# APRS-ESP32_SA8x8_Rev_D.net
KiCad netlist of a schematic drawn in EAGLE
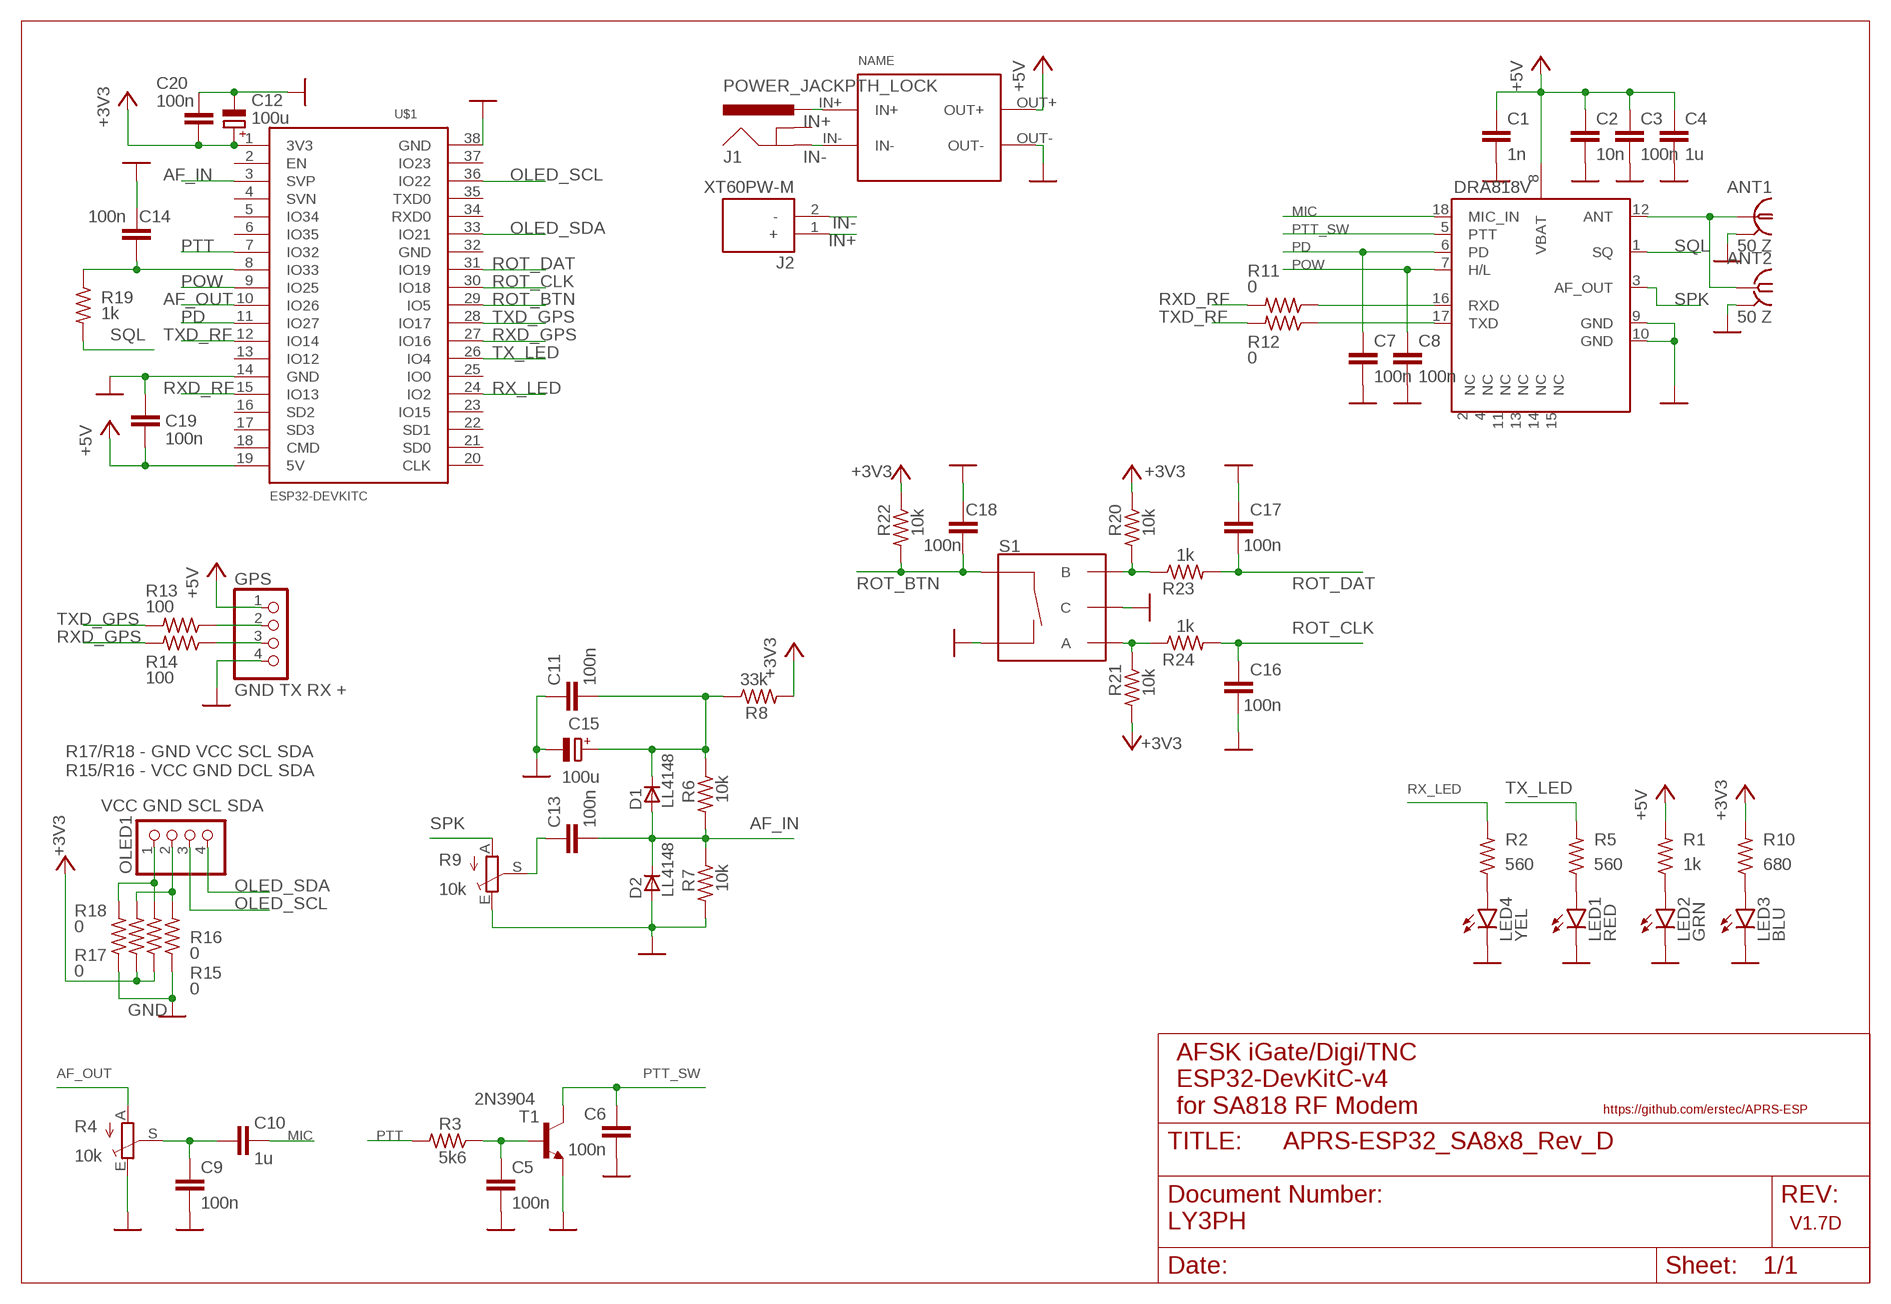
[diagram p0: schematic, sheet 1]

(export (version "E")
  (design (tool "Eeschema 10.0.6"))
  (components
    (comp (ref "ANT1")
      (value "50 Z")
      (footprint "eagle-import:LTI-SASF54GT")
      (libsource (lib "eagle-import") (part "LTI-SASF54GT"))
    )
    (comp (ref "ANT2")
      (value "50 Z")
      (footprint "eagle-import:J502-ND-142-0701-801_806")
      (fields (field (name "MF") "JOHNSON COMPONENTS") (field (name "MPN") "142-0701-801"))
      (libsource (lib "eagle-import") (part "SMA-142-0701-801/806"))
    )
    (comp (ref "C1")
      (value "1n")
      (footprint "eagle-import:C0805")
      (libsource (lib "eagle-import") (part "C-EUC0805"))
    )
    (comp (ref "C2")
      (value "10n")
      (footprint "eagle-import:C0805")
      (libsource (lib "eagle-import") (part "C-EUC0805"))
    )
    (comp (ref "C3")
      (value "100n")
      (footprint "eagle-import:C0805")
      (libsource (lib "eagle-import") (part "C-EUC0805"))
    )
    (comp (ref "C4")
      (value "1u")
      (footprint "eagle-import:C0805")
      (libsource (lib "eagle-import") (part "C-EUC0805"))
    )
    (comp (ref "C5")
      (value "100n")
      (footprint "eagle-import:C0805")
      (libsource (lib "eagle-import") (part "C-EUC0805"))
    )
    (comp (ref "C6")
      (value "100n")
      (footprint "eagle-import:C0805")
      (libsource (lib "eagle-import") (part "C-EUC0805"))
    )
    (comp (ref "C7")
      (value "100n")
      (footprint "eagle-import:C0805")
      (libsource (lib "eagle-import") (part "C-EUC0805"))
    )
    (comp (ref "C8")
      (value "100n")
      (footprint "eagle-import:C0805")
      (libsource (lib "eagle-import") (part "C-EUC0805"))
    )
    (comp (ref "C9")
      (value "100n")
      (footprint "eagle-import:C0805")
      (libsource (lib "eagle-import") (part "C-EUC0805"))
    )
    (comp (ref "C10")
      (value "1u")
      (footprint "eagle-import:C0805")
      (libsource (lib "eagle-import") (part "C-EUC0805"))
    )
    (comp (ref "C11")
      (value "100n")
      (footprint "eagle-import:C0805")
      (libsource (lib "eagle-import") (part "C-EUC0805"))
    )
    (comp (ref "C12")
      (value "100u")
      (footprint "eagle-import:SMC_D")
      (libsource (lib "eagle-import") (part "CPOL-EUSMCD"))
    )
    (comp (ref "C13")
      (value "100n")
      (footprint "eagle-import:C0805")
      (libsource (lib "eagle-import") (part "C-EUC0805"))
    )
    (comp (ref "C14")
      (value "100n")
      (footprint "eagle-import:C0805")
      (libsource (lib "eagle-import") (part "C-EUC0805"))
    )
    (comp (ref "C15")
      (value "100u")
      (footprint "eagle-import:SMC_D")
      (libsource (lib "eagle-import") (part "CPOL-EUSMCD"))
    )
    (comp (ref "C16")
      (value "100n")
      (footprint "eagle-import:C0805")
      (libsource (lib "eagle-import") (part "C-EUC0805"))
    )
    (comp (ref "C17")
      (value "100n")
      (footprint "eagle-import:C0805")
      (libsource (lib "eagle-import") (part "C-EUC0805"))
    )
    (comp (ref "C18")
      (value "100n")
      (footprint "eagle-import:C0805")
      (libsource (lib "eagle-import") (part "C-EUC0805"))
    )
    (comp (ref "C19")
      (value "100n")
      (footprint "eagle-import:C0805")
      (libsource (lib "eagle-import") (part "C-EUC0805"))
    )
    (comp (ref "C20")
      (value "100n")
      (footprint "eagle-import:C0805")
      (libsource (lib "eagle-import") (part "C-EUC0805"))
    )
    (comp (ref "D1")
      (value "LL4148")
      (footprint "eagle-import:SOD80_DO213AA_MINIMELF")
      (libsource (lib "eagle-import") (part "LL4148"))
    )
    (comp (ref "D2")
      (value "LL4148")
      (footprint "eagle-import:SOD80_DO213AA_MINIMELF")
      (libsource (lib "eagle-import") (part "LL4148"))
    )
    (comp (ref "DRA818V")
      (value "DRA818A")
      (footprint "eagle-import:DRA818A")
      (libsource (lib "eagle-import") (part "DRA818A"))
    )
    (comp (ref "GPS")
      (value "GND TX RX +")
      (footprint "eagle-import:1X04")
      (libsource (lib "eagle-import") (part "PINHD-1X4"))
    )
    (comp (ref "J1")
      (value "POWER_JACKPTH_LOCK")
      (footprint "eagle-import:POWER_JACK_PTH_LOCK")
      (libsource (lib "eagle-import") (part "POWER_JACKPTH_LOCK"))
    )
    (comp (ref "J2")
      (value "XT60PW-M")
      (footprint "eagle-import:AMASS_XT60PW-M")
      (fields (field (name "MF") "AMASS"))
      (libsource (lib "eagle-import") (part "XT60PW-M"))
    )
    (comp (ref "LED1")
      (value "RED")
      (footprint "eagle-import:CHIP-LED0805")
      (libsource (lib "eagle-import") (part "LEDCHIP-LED0805"))
    )
    (comp (ref "LED2")
      (value "GRN")
      (footprint "eagle-import:CHIP-LED0805")
      (libsource (lib "eagle-import") (part "LEDCHIP-LED0805"))
    )
    (comp (ref "LED3")
      (value "BLU")
      (footprint "eagle-import:CHIP-LED0805")
      (libsource (lib "eagle-import") (part "LEDCHIP-LED0805"))
    )
    (comp (ref "LED4")
      (value "YEL")
      (footprint "eagle-import:CHIP-LED0805")
      (libsource (lib "eagle-import") (part "LEDCHIP-LED0805"))
    )
    (comp (ref "OLED1")
      (value "VCC GND SCL SDA")
      (footprint "eagle-import:1X04")
      (libsource (lib "eagle-import") (part "PINHD-1X4"))
    )
    (comp (ref "R1")
      (value "1k")
      (footprint "eagle-import:R0805")
      (libsource (lib "eagle-import") (part "R-US_R0805"))
    )
    (comp (ref "R2")
      (value "560")
      (footprint "eagle-import:R0805")
      (libsource (lib "eagle-import") (part "R-US_R0805"))
    )
    (comp (ref "R3")
      (value "5k6")
      (footprint "eagle-import:R0805")
      (libsource (lib "eagle-import") (part "R-US_R0805"))
    )
    (comp (ref "R4")
      (value "10k")
      (footprint "eagle-import:CA6H")
      (libsource (lib "eagle-import") (part "TRIM_EU-CA6H"))
    )
    (comp (ref "R5")
      (value "560")
      (footprint "eagle-import:R0805")
      (libsource (lib "eagle-import") (part "R-US_R0805"))
    )
    (comp (ref "R6")
      (value "10k")
      (footprint "eagle-import:R0805")
      (libsource (lib "eagle-import") (part "R-US_R0805"))
    )
    (comp (ref "R7")
      (value "10k")
      (footprint "eagle-import:R0805")
      (libsource (lib "eagle-import") (part "R-US_R0805"))
    )
    (comp (ref "R8")
      (value "33k")
      (footprint "eagle-import:R0805")
      (libsource (lib "eagle-import") (part "R-US_R0805"))
    )
    (comp (ref "R9")
      (value "10k")
      (footprint "eagle-import:CA6H")
      (libsource (lib "eagle-import") (part "TRIM_EU-CA6H"))
    )
    (comp (ref "R10")
      (value "680")
      (footprint "eagle-import:R0805")
      (libsource (lib "eagle-import") (part "R-US_R0805"))
    )
    (comp (ref "R11")
      (value "0")
      (footprint "eagle-import:R0805")
      (libsource (lib "eagle-import") (part "R-US_R0805"))
    )
    (comp (ref "R12")
      (value "0")
      (footprint "eagle-import:R0805")
      (libsource (lib "eagle-import") (part "R-US_R0805"))
    )
    (comp (ref "R13")
      (value "100")
      (footprint "eagle-import:R0805")
      (libsource (lib "eagle-import") (part "R-US_R0805"))
    )
    (comp (ref "R14")
      (value "100")
      (footprint "eagle-import:R0805")
      (libsource (lib "eagle-import") (part "R-US_R0805"))
    )
    (comp (ref "R15")
      (value "0")
      (footprint "eagle-import:R0805")
      (libsource (lib "eagle-import") (part "R-US_R0805"))
    )
    (comp (ref "R16")
      (value "0")
      (footprint "eagle-import:R0805")
      (libsource (lib "eagle-import") (part "R-US_R0805"))
    )
    (comp (ref "R17")
      (value "0")
      (footprint "eagle-import:R0805")
      (libsource (lib "eagle-import") (part "R-US_R0805"))
    )
    (comp (ref "R18")
      (value "0")
      (footprint "eagle-import:R0805")
      (libsource (lib "eagle-import") (part "R-US_R0805"))
    )
    (comp (ref "R19")
      (value "1k")
      (footprint "eagle-import:R0805")
      (libsource (lib "eagle-import") (part "R-US_R0805"))
    )
    (comp (ref "R20")
      (value "10k")
      (footprint "eagle-import:R0805")
      (libsource (lib "eagle-import") (part "R-US_R0805"))
    )
    (comp (ref "R21")
      (value "10k")
      (footprint "eagle-import:R0805")
      (libsource (lib "eagle-import") (part "R-US_R0805"))
    )
    (comp (ref "R22")
      (value "10k")
      (footprint "eagle-import:R0805")
      (libsource (lib "eagle-import") (part "R-US_R0805"))
    )
    (comp (ref "R23")
      (value "1k")
      (footprint "eagle-import:R0805")
      (libsource (lib "eagle-import") (part "R-US_R0805"))
    )
    (comp (ref "R24")
      (value "1k")
      (footprint "eagle-import:R0805")
      (libsource (lib "eagle-import") (part "R-US_R0805"))
    )
    (comp (ref "S1")
      (value "ENCODER-SWITCH")
      (footprint "eagle-import:ROTARY_ENC_PLAIN")
      (libsource (lib "eagle-import") (part "ENCODER-SWITCH"))
    )
    (comp (ref "T1")
      (value "2N3904")
      (footprint "eagle-import:SOT23-BEC")
      (libsource (lib "eagle-import") (part "-NPN-SOT23-BECMMBT3904LT1"))
    )
    (comp (ref "U$1")
      (value "ESP32DEVKITC")
      (footprint "eagle-import:ESP32-DEVKITC")
      (libsource (lib "eagle-import") (part "ESP32DEVKITC"))
    )
    (comp (ref "U$2")
      (value "CP8-ADJ")
      (footprint "eagle-import:CP8-ADJ")
      (libsource (lib "eagle-import") (part "CP8-ADJ"))
    )
  )
  (nets
    (net (code "1") (name "+3V3") (class "Default")
      (node (ref "C12") (pin "+") (pinfunction "+_+") (pintype "passive"))
      (node (ref "C20") (pin "2") (pinfunction "2_2") (pintype "passive"))
      (node (ref "R10") (pin "2") (pinfunction "2_2") (pintype "passive"))
      (node (ref "R15") (pin "1") (pinfunction "1_1") (pintype "passive"))
      (node (ref "R17") (pin "1") (pinfunction "1_1") (pintype "passive"))
      (node (ref "R20") (pin "1") (pinfunction "1_1") (pintype "passive"))
      (node (ref "R21") (pin "2") (pinfunction "2_2") (pintype "passive"))
      (node (ref "R22") (pin "1") (pinfunction "1_1") (pintype "passive"))
      (node (ref "R8") (pin "2") (pinfunction "2_2") (pintype "passive"))
      (node (ref "U$1") (pin "1") (pinfunction "3V3_1") (pintype "bidirectional"))
    )
    (net (code "2") (name "+5V") (class "Default")
      (node (ref "C1") (pin "1") (pinfunction "1_1") (pintype "passive"))
      (node (ref "C19") (pin "2") (pinfunction "2_2") (pintype "passive"))
      (node (ref "C2") (pin "1") (pinfunction "1_1") (pintype "passive"))
      (node (ref "C3") (pin "1") (pinfunction "1_1") (pintype "passive"))
      (node (ref "C4") (pin "1") (pinfunction "1_1") (pintype "passive"))
      (node (ref "DRA818V") (pin "8") (pinfunction "VBAT_8") (pintype "bidirectional"))
      (node (ref "GPS") (pin "1") (pinfunction "1_1") (pintype "passive"))
      (node (ref "R1") (pin "2") (pinfunction "2_2") (pintype "passive"))
      (node (ref "U$1") (pin "19") (pinfunction "5V_19") (pintype "bidirectional"))
      (node (ref "U$2") (pin "OUT+") (pinfunction "OUT+_OUT+") (pintype "passive"))
    )
    (net (code "3") (name "/AF_IN") (class "Default")
      (node (ref "C13") (pin "2") (pinfunction "2_2") (pintype "passive"))
      (node (ref "D1") (pin "A") (pinfunction "A_A") (pintype "passive"))
      (node (ref "D2") (pin "C") (pinfunction "C_C") (pintype "passive"))
      (node (ref "R6") (pin "2") (pinfunction "2_2") (pintype "passive"))
      (node (ref "R7") (pin "1") (pinfunction "1_1") (pintype "passive"))
      (node (ref "U$1") (pin "3") (pinfunction "SVP_3") (pintype "bidirectional"))
    )
    (net (code "4") (name "/AF_OUT") (class "Default")
      (node (ref "R4") (pin "A") (pinfunction "A_A") (pintype "passive"))
      (node (ref "U$1") (pin "10") (pinfunction "IO26_10") (pintype "bidirectional"))
    )
    (net (code "5") (name "/IN+") (class "Default")
      (node (ref "J1") (pin "PWR") (pinfunction "PWR_PWR") (pintype "bidirectional"))
      (node (ref "J2") (pin "1") (pinfunction "+_1") (pintype "passive"))
      (node (ref "U$2") (pin "IN+") (pinfunction "IN+_IN+") (pintype "passive"))
    )
    (net (code "6") (name "/IN-") (class "Default")
      (node (ref "J1") (pin "GND") (pinfunction "GND_GND") (pintype "bidirectional"))
      (node (ref "J2") (pin "2") (pinfunction "-_2") (pintype "passive"))
      (node (ref "U$2") (pin "IN-") (pinfunction "IN-_IN-") (pintype "passive"))
    )
    (net (code "7") (name "/MIC") (class "Default")
      (node (ref "C10") (pin "2") (pinfunction "2_2") (pintype "passive"))
      (node (ref "DRA818V") (pin "18") (pinfunction "MIC_IN_18") (pintype "bidirectional"))
    )
    (net (code "8") (name "/OLED_SCL") (class "Default")
      (node (ref "OLED1") (pin "3") (pinfunction "3_3") (pintype "passive"))
      (node (ref "U$1") (pin "36") (pinfunction "IO22_36") (pintype "bidirectional"))
    )
    (net (code "9") (name "/OLED_SDA") (class "Default")
      (node (ref "OLED1") (pin "4") (pinfunction "4_4") (pintype "passive"))
      (node (ref "U$1") (pin "33") (pinfunction "IO21_33") (pintype "bidirectional"))
    )
    (net (code "10") (name "/PD") (class "Default")
      (node (ref "C7") (pin "1") (pinfunction "1_1") (pintype "passive"))
      (node (ref "DRA818V") (pin "6") (pinfunction "PD_6") (pintype "bidirectional"))
      (node (ref "U$1") (pin "11") (pinfunction "IO27_11") (pintype "bidirectional"))
    )
    (net (code "11") (name "/POW") (class "Default")
      (node (ref "C8") (pin "1") (pinfunction "1_1") (pintype "passive"))
      (node (ref "DRA818V") (pin "7") (pinfunction "H/L_7") (pintype "bidirectional"))
      (node (ref "U$1") (pin "9") (pinfunction "IO25_9") (pintype "bidirectional"))
    )
    (net (code "12") (name "/PTT") (class "Default")
      (node (ref "R3") (pin "2") (pinfunction "2_2") (pintype "passive"))
      (node (ref "U$1") (pin "7") (pinfunction "IO32_7") (pintype "bidirectional"))
    )
    (net (code "13") (name "/PTT_SW") (class "Default")
      (node (ref "C6") (pin "1") (pinfunction "1_1") (pintype "passive"))
      (node (ref "DRA818V") (pin "5") (pinfunction "PTT_5") (pintype "bidirectional"))
      (node (ref "T1") (pin "C") (pinfunction "C_C") (pintype "passive"))
    )
    (net (code "14") (name "/ROT_BTN") (class "Default")
      (node (ref "C18") (pin "2") (pinfunction "2_2") (pintype "passive"))
      (node (ref "R22") (pin "2") (pinfunction "2_2") (pintype "passive"))
      (node (ref "S1") (pin "SW+") (pinfunction "SW+_SW+") (pintype "bidirectional"))
      (node (ref "U$1") (pin "29") (pinfunction "IO5_29") (pintype "bidirectional"))
    )
    (net (code "15") (name "/ROT_CLK") (class "Default")
      (node (ref "C16") (pin "1") (pinfunction "1_1") (pintype "passive"))
      (node (ref "R24") (pin "2") (pinfunction "2_2") (pintype "passive"))
      (node (ref "U$1") (pin "30") (pinfunction "IO18_30") (pintype "bidirectional"))
    )
    (net (code "16") (name "/ROT_DAT") (class "Default")
      (node (ref "C17") (pin "2") (pinfunction "2_2") (pintype "passive"))
      (node (ref "R23") (pin "2") (pinfunction "2_2") (pintype "passive"))
      (node (ref "U$1") (pin "31") (pinfunction "IO19_31") (pintype "bidirectional"))
    )
    (net (code "17") (name "/RXD_GPS") (class "Default")
      (node (ref "R14") (pin "2") (pinfunction "2_2") (pintype "passive"))
      (node (ref "U$1") (pin "27") (pinfunction "IO16_27") (pintype "bidirectional"))
    )
    (net (code "18") (name "/RXD_RF") (class "Default")
      (node (ref "R11") (pin "2") (pinfunction "2_2") (pintype "passive"))
      (node (ref "U$1") (pin "15") (pinfunction "IO13_15") (pintype "bidirectional"))
    )
    (net (code "19") (name "/RX_LED") (class "Default")
      (node (ref "R2") (pin "2") (pinfunction "2_2") (pintype "passive"))
      (node (ref "U$1") (pin "24") (pinfunction "IO2_24") (pintype "bidirectional"))
    )
    (net (code "20") (name "/SPK") (class "Default")
      (node (ref "DRA818V") (pin "3") (pinfunction "AF_OUT_3") (pintype "bidirectional"))
      (node (ref "R9") (pin "A") (pinfunction "A_A") (pintype "passive"))
    )
    (net (code "21") (name "/SQL") (class "Default")
      (node (ref "DRA818V") (pin "1") (pinfunction "SQ_1") (pintype "bidirectional"))
      (node (ref "R19") (pin "2") (pinfunction "2_2") (pintype "passive"))
    )
    (net (code "22") (name "/TXD_GPS") (class "Default")
      (node (ref "R13") (pin "2") (pinfunction "2_2") (pintype "passive"))
      (node (ref "U$1") (pin "28") (pinfunction "IO17_28") (pintype "bidirectional"))
    )
    (net (code "23") (name "/TXD_RF") (class "Default")
      (node (ref "R12") (pin "2") (pinfunction "2_2") (pintype "passive"))
      (node (ref "U$1") (pin "12") (pinfunction "IO14_12") (pintype "bidirectional"))
    )
    (net (code "24") (name "/TX_LED") (class "Default")
      (node (ref "R5") (pin "2") (pinfunction "2_2") (pintype "passive"))
      (node (ref "U$1") (pin "26") (pinfunction "IO4_26") (pintype "bidirectional"))
    )
    (net (code "25") (name "GND") (class "Default")
      (node (ref "ANT1") (pin "2") (pinfunction "2_2") (pintype "passive"))
      (node (ref "ANT1") (pin "3") (pinfunction "2_3") (pintype "passive"))
      (node (ref "ANT1") (pin "4") (pinfunction "2_4") (pintype "passive"))
      (node (ref "ANT1") (pin "5") (pinfunction "2_5") (pintype "passive"))
      (node (ref "ANT2") (pin "G@1") (pinfunction "2_G@1") (pintype "passive"))
      (node (ref "ANT2") (pin "G@2") (pinfunction "2_G@2") (pintype "passive"))
      (node (ref "ANT2") (pin "G@3") (pinfunction "2_G@3") (pintype "passive"))
      (node (ref "ANT2") (pin "G@4") (pinfunction "2_G@4") (pintype "passive"))
      (node (ref "C1") (pin "2") (pinfunction "2_2") (pintype "passive"))
      (node (ref "C11") (pin "1") (pinfunction "1_1") (pintype "passive"))
      (node (ref "C12") (pin "-") (pinfunction "-_-") (pintype "passive"))
      (node (ref "C14") (pin "2") (pinfunction "2_2") (pintype "passive"))
      (node (ref "C15") (pin "-") (pinfunction "-_-") (pintype "passive"))
      (node (ref "C16") (pin "2") (pinfunction "2_2") (pintype "passive"))
      (node (ref "C17") (pin "1") (pinfunction "1_1") (pintype "passive"))
      (node (ref "C18") (pin "1") (pinfunction "1_1") (pintype "passive"))
      (node (ref "C19") (pin "1") (pinfunction "1_1") (pintype "passive"))
      (node (ref "C2") (pin "2") (pinfunction "2_2") (pintype "passive"))
      (node (ref "C20") (pin "1") (pinfunction "1_1") (pintype "passive"))
      (node (ref "C3") (pin "2") (pinfunction "2_2") (pintype "passive"))
      (node (ref "C4") (pin "2") (pinfunction "2_2") (pintype "passive"))
      (node (ref "C5") (pin "2") (pinfunction "2_2") (pintype "passive"))
      (node (ref "C6") (pin "2") (pinfunction "2_2") (pintype "passive"))
      (node (ref "C7") (pin "2") (pinfunction "2_2") (pintype "passive"))
      (node (ref "C8") (pin "2") (pinfunction "2_2") (pintype "passive"))
      (node (ref "C9") (pin "2") (pinfunction "2_2") (pintype "passive"))
      (node (ref "D2") (pin "A") (pinfunction "A_A") (pintype "passive"))
      (node (ref "DRA818V") (pin "10") (pinfunction "GND_10") (pintype "bidirectional"))
      (node (ref "DRA818V") (pin "9") (pinfunction "GND_9") (pintype "bidirectional"))
      (node (ref "GPS") (pin "4") (pinfunction "4_4") (pintype "passive"))
      (node (ref "LED1") (pin "C") (pinfunction "C_C") (pintype "passive"))
      (node (ref "LED2") (pin "C") (pinfunction "C_C") (pintype "passive"))
      (node (ref "LED3") (pin "C") (pinfunction "C_C") (pintype "passive"))
      (node (ref "LED4") (pin "C") (pinfunction "C_C") (pintype "passive"))
      (node (ref "R16") (pin "1") (pinfunction "1_1") (pintype "passive"))
      (node (ref "R18") (pin "1") (pinfunction "1_1") (pintype "passive"))
      (node (ref "R4") (pin "E") (pinfunction "E_E") (pintype "passive"))
      (node (ref "R7") (pin "2") (pinfunction "2_2") (pintype "passive"))
      (node (ref "R9") (pin "E") (pinfunction "E_E") (pintype "passive"))
      (node (ref "S1") (pin "C") (pinfunction "C_C") (pintype "bidirectional"))
      (node (ref "S1") (pin "SW-") (pinfunction "SW-_SW-") (pintype "bidirectional"))
      (node (ref "T1") (pin "E") (pinfunction "E_E") (pintype "passive"))
      (node (ref "U$1") (pin "14") (pinfunction "GND_14") (pintype "bidirectional"))
      (node (ref "U$1") (pin "38") (pinfunction "GND_38") (pintype "bidirectional"))
      (node (ref "U$2") (pin "OUT-") (pinfunction "OUT-_OUT-") (pintype "passive"))
    )
    (net (code "26") (name "Net-(C5-Pad1)") (class "Default")
      (node (ref "C5") (pin "1") (pinfunction "1_1") (pintype "passive"))
      (node (ref "R3") (pin "1") (pinfunction "1_1") (pintype "passive"))
      (node (ref "T1") (pin "B") (pinfunction "B_B") (pintype "passive"))
    )
    (net (code "27") (name "Net-(C10-Pad1)") (class "Default")
      (node (ref "C10") (pin "1") (pinfunction "1_1") (pintype "passive"))
      (node (ref "C9") (pin "1") (pinfunction "1_1") (pintype "passive"))
      (node (ref "R4") (pin "S") (pinfunction "S_S") (pintype "passive"))
    )
    (net (code "28") (name "Net-(C11-Pad2)") (class "Default")
      (node (ref "C11") (pin "2") (pinfunction "2_2") (pintype "passive"))
      (node (ref "C15") (pin "+") (pinfunction "+_+") (pintype "passive"))
      (node (ref "D1") (pin "C") (pinfunction "C_C") (pintype "passive"))
      (node (ref "R6") (pin "1") (pinfunction "1_1") (pintype "passive"))
      (node (ref "R8") (pin "1") (pinfunction "1_1") (pintype "passive"))
    )
    (net (code "29") (name "Net-(C13-Pad1)") (class "Default")
      (node (ref "C13") (pin "1") (pinfunction "1_1") (pintype "passive"))
      (node (ref "R9") (pin "S") (pinfunction "S_S") (pintype "passive"))
    )
    (net (code "30") (name "Net-(DRA818V-ANT)") (class "Default")
      (node (ref "ANT1") (pin "1") (pinfunction "1_1") (pintype "passive"))
      (node (ref "ANT2") (pin "1") (pinfunction "1_1") (pintype "passive"))
      (node (ref "DRA818V") (pin "12") (pinfunction "ANT_12") (pintype "bidirectional"))
    )
    (net (code "31") (name "Net-(DRA818V-RXD)") (class "Default")
      (node (ref "DRA818V") (pin "16") (pinfunction "RXD_16") (pintype "bidirectional"))
      (node (ref "R11") (pin "1") (pinfunction "1_1") (pintype "passive"))
    )
    (net (code "32") (name "Net-(DRA818V-TXD)") (class "Default")
      (node (ref "DRA818V") (pin "17") (pinfunction "TXD_17") (pintype "bidirectional"))
      (node (ref "R12") (pin "1") (pinfunction "1_1") (pintype "passive"))
    )
    (net (code "33") (name "Net-(GPS-Pad2)") (class "Default")
      (node (ref "GPS") (pin "2") (pinfunction "2_2") (pintype "passive"))
      (node (ref "R13") (pin "1") (pinfunction "1_1") (pintype "passive"))
    )
    (net (code "34") (name "Net-(GPS-Pad3)") (class "Default")
      (node (ref "GPS") (pin "3") (pinfunction "3_3") (pintype "passive"))
      (node (ref "R14") (pin "1") (pinfunction "1_1") (pintype "passive"))
    )
    (net (code "35") (name "Net-(LED1-PadA)") (class "Default")
      (node (ref "LED1") (pin "A") (pinfunction "A_A") (pintype "passive"))
      (node (ref "R5") (pin "1") (pinfunction "1_1") (pintype "passive"))
    )
    (net (code "36") (name "Net-(LED2-PadA)") (class "Default")
      (node (ref "LED2") (pin "A") (pinfunction "A_A") (pintype "passive"))
      (node (ref "R1") (pin "1") (pinfunction "1_1") (pintype "passive"))
    )
    (net (code "37") (name "Net-(LED3-PadA)") (class "Default")
      (node (ref "LED3") (pin "A") (pinfunction "A_A") (pintype "passive"))
      (node (ref "R10") (pin "1") (pinfunction "1_1") (pintype "passive"))
    )
    (net (code "38") (name "Net-(LED4-PadA)") (class "Default")
      (node (ref "LED4") (pin "A") (pinfunction "A_A") (pintype "passive"))
      (node (ref "R2") (pin "1") (pinfunction "1_1") (pintype "passive"))
    )
    (net (code "39") (name "Net-(OLED1-Pad1)") (class "Default")
      (node (ref "OLED1") (pin "1") (pinfunction "1_1") (pintype "passive"))
      (node (ref "R15") (pin "2") (pinfunction "2_2") (pintype "passive"))
      (node (ref "R18") (pin "2") (pinfunction "2_2") (pintype "passive"))
    )
    (net (code "40") (name "Net-(OLED1-Pad2)") (class "Default")
      (node (ref "OLED1") (pin "2") (pinfunction "2_2") (pintype "passive"))
      (node (ref "R16") (pin "2") (pinfunction "2_2") (pintype "passive"))
      (node (ref "R17") (pin "2") (pinfunction "2_2") (pintype "passive"))
    )
    (net (code "41") (name "Net-(R20-Pad2)") (class "Default")
      (node (ref "R20") (pin "2") (pinfunction "2_2") (pintype "passive"))
      (node (ref "R23") (pin "1") (pinfunction "1_1") (pintype "passive"))
      (node (ref "S1") (pin "B") (pinfunction "B_B") (pintype "bidirectional"))
    )
    (net (code "42") (name "Net-(R21-Pad1)") (class "Default")
      (node (ref "R21") (pin "1") (pinfunction "1_1") (pintype "passive"))
      (node (ref "R24") (pin "1") (pinfunction "1_1") (pintype "passive"))
      (node (ref "S1") (pin "A") (pinfunction "A_A") (pintype "bidirectional"))
    )
    (net (code "43") (name "Net-(U$1-IO33)") (class "Default")
      (node (ref "C14") (pin "1") (pinfunction "1_1") (pintype "passive"))
      (node (ref "R19") (pin "1") (pinfunction "1_1") (pintype "passive"))
      (node (ref "U$1") (pin "8") (pinfunction "IO33_8") (pintype "bidirectional"))
    )
    (net (code "44") (name "unconnected-(DRA818V-NC-Pad2)") (class "Default")
      (node (ref "DRA818V") (pin "2") (pinfunction "NC_2") (pintype "bidirectional"))
    )
    (net (code "45") (name "unconnected-(DRA818V-NC-Pad4)") (class "Default")
      (node (ref "DRA818V") (pin "4") (pinfunction "NC_4") (pintype "bidirectional"))
    )
    (net (code "46") (name "unconnected-(DRA818V-NC-Pad11)") (class "Default")
      (node (ref "DRA818V") (pin "11") (pinfunction "NC_11") (pintype "bidirectional"))
    )
    (net (code "47") (name "unconnected-(DRA818V-NC-Pad13)") (class "Default")
      (node (ref "DRA818V") (pin "13") (pinfunction "NC_13") (pintype "bidirectional"))
    )
    (net (code "48") (name "unconnected-(DRA818V-NC-Pad14)") (class "Default")
      (node (ref "DRA818V") (pin "14") (pinfunction "NC_14") (pintype "bidirectional"))
    )
    (net (code "49") (name "unconnected-(DRA818V-NC-Pad15)") (class "Default")
      (node (ref "DRA818V") (pin "15") (pinfunction "NC_15") (pintype "bidirectional"))
    )
    (net (code "50") (name "unconnected-(J1-PadGNDBREAK)") (class "Default")
      (node (ref "J1") (pin "GNDBREAK") (pinfunction "GNDBREAK_GNDBREAK") (pintype "bidirectional"))
    )
    (net (code "51") (name "unconnected-(U$1-CLK-Pad20)") (class "Default")
      (node (ref "U$1") (pin "20") (pinfunction "CLK_20") (pintype "bidirectional"))
    )
    (net (code "52") (name "unconnected-(U$1-CMD-Pad18)") (class "Default")
      (node (ref "U$1") (pin "18") (pinfunction "CMD_18") (pintype "bidirectional"))
    )
    (net (code "53") (name "unconnected-(U$1-EN-Pad2)") (class "Default")
      (node (ref "U$1") (pin "2") (pinfunction "EN_2") (pintype "bidirectional"))
    )
    (net (code "54") (name "unconnected-(U$1-GND-Pad32)") (class "Default")
      (node (ref "U$1") (pin "32") (pinfunction "GND_32") (pintype "bidirectional"))
    )
    (net (code "55") (name "unconnected-(U$1-IO0-Pad25)") (class "Default")
      (node (ref "U$1") (pin "25") (pinfunction "IO0_25") (pintype "bidirectional"))
    )
    (net (code "56") (name "unconnected-(U$1-IO12-Pad13)") (class "Default")
      (node (ref "U$1") (pin "13") (pinfunction "IO12_13") (pintype "bidirectional"))
    )
    (net (code "57") (name "unconnected-(U$1-IO15-Pad23)") (class "Default")
      (node (ref "U$1") (pin "23") (pinfunction "IO15_23") (pintype "bidirectional"))
    )
    (net (code "58") (name "unconnected-(U$1-IO23-Pad37)") (class "Default")
      (node (ref "U$1") (pin "37") (pinfunction "IO23_37") (pintype "bidirectional"))
    )
    (net (code "59") (name "unconnected-(U$1-IO34-Pad5)") (class "Default")
      (node (ref "U$1") (pin "5") (pinfunction "IO34_5") (pintype "bidirectional"))
    )
    (net (code "60") (name "unconnected-(U$1-IO35-Pad6)") (class "Default")
      (node (ref "U$1") (pin "6") (pinfunction "IO35_6") (pintype "bidirectional"))
    )
    (net (code "61") (name "unconnected-(U$1-RXD0-Pad34)") (class "Default")
      (node (ref "U$1") (pin "34") (pinfunction "RXD0_34") (pintype "bidirectional"))
    )
    (net (code "62") (name "unconnected-(U$1-SD0-Pad21)") (class "Default")
      (node (ref "U$1") (pin "21") (pinfunction "SD0_21") (pintype "bidirectional"))
    )
    (net (code "63") (name "unconnected-(U$1-SD1-Pad22)") (class "Default")
      (node (ref "U$1") (pin "22") (pinfunction "SD1_22") (pintype "bidirectional"))
    )
    (net (code "64") (name "unconnected-(U$1-SD2-Pad16)") (class "Default")
      (node (ref "U$1") (pin "16") (pinfunction "SD2_16") (pintype "bidirectional"))
    )
    (net (code "65") (name "unconnected-(U$1-SD3-Pad17)") (class "Default")
      (node (ref "U$1") (pin "17") (pinfunction "SD3_17") (pintype "bidirectional"))
    )
    (net (code "66") (name "unconnected-(U$1-SVN-Pad4)") (class "Default")
      (node (ref "U$1") (pin "4") (pinfunction "SVN_4") (pintype "bidirectional"))
    )
    (net (code "67") (name "unconnected-(U$1-TXD0-Pad35)") (class "Default")
      (node (ref "U$1") (pin "35") (pinfunction "TXD0_35") (pintype "bidirectional"))
    )
  )
)
